# RFID_bmd200.net
KiCad netlist of a schematic drawn in EAGLE
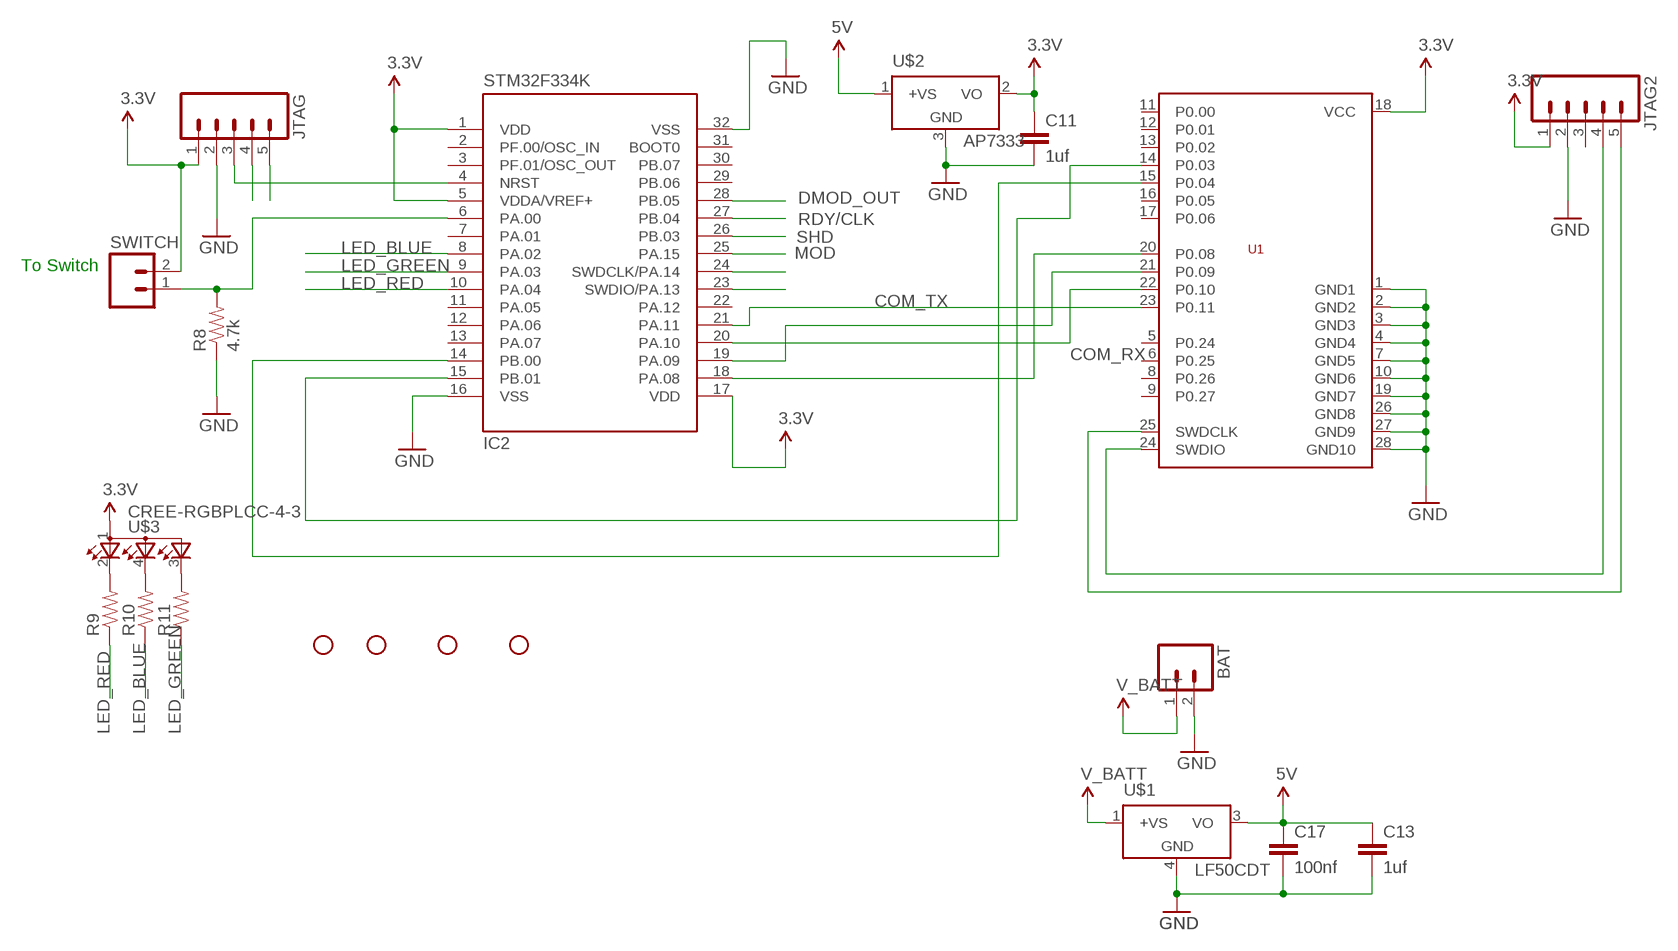
[diagram p0: schematic, sheet 1]
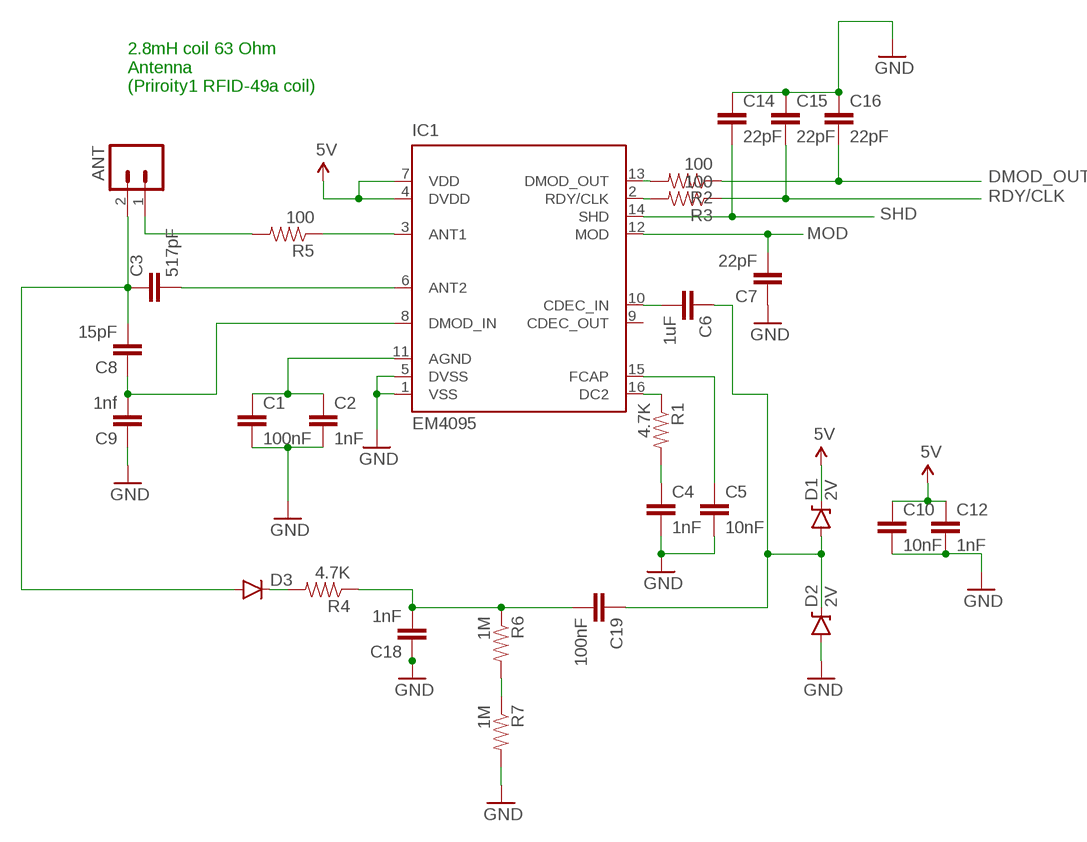
[diagram p1: schematic, sheet 2]

(export (version "E")
  (design (tool "Eeschema 10.0.6"))
  (components
    (comp (ref "ANT")
      (value "M02PTH")
      (footprint "eagle-import:1X02")
      (libsource (lib "eagle-import") (part "M02PTH"))
    )
    (comp (ref "C1")
      (value "100nF")
      (footprint "eagle-import:0805")
      (libsource (lib "eagle-import") (part "CAP0805"))
    )
    (comp (ref "C2")
      (value "1nF")
      (footprint "eagle-import:0805")
      (libsource (lib "eagle-import") (part "CAP0805"))
    )
    (comp (ref "C3")
      (value "517pF")
      (footprint "eagle-import:0805")
      (libsource (lib "eagle-import") (part "CAP0805"))
    )
    (comp (ref "C4")
      (value "1nF")
      (footprint "eagle-import:0805")
      (libsource (lib "eagle-import") (part "CAP0805"))
    )
    (comp (ref "C5")
      (value "10nF")
      (footprint "eagle-import:0805")
      (libsource (lib "eagle-import") (part "CAP0805"))
    )
    (comp (ref "C6")
      (value "1uF")
      (footprint "eagle-import:0805")
      (libsource (lib "eagle-import") (part "CAP0805"))
    )
    (comp (ref "C7")
      (value "22pF")
      (footprint "eagle-import:0805")
      (libsource (lib "eagle-import") (part "CAP0805"))
    )
    (comp (ref "C8")
      (value "15pF")
      (footprint "eagle-import:0805")
      (libsource (lib "eagle-import") (part "CAP0805"))
    )
    (comp (ref "C9")
      (value "1nf")
      (footprint "eagle-import:0805")
      (libsource (lib "eagle-import") (part "CAP0805"))
    )
    (comp (ref "C10")
      (value "10nF")
      (footprint "eagle-import:0805")
      (libsource (lib "eagle-import") (part "CAP0805"))
    )
    (comp (ref "C12")
      (value "1nF")
      (footprint "eagle-import:0805")
      (libsource (lib "eagle-import") (part "CAP0805"))
    )
    (comp (ref "C14")
      (value "22pF")
      (footprint "eagle-import:0805")
      (libsource (lib "eagle-import") (part "CAP0805"))
    )
    (comp (ref "C15")
      (value "22pF")
      (footprint "eagle-import:0805")
      (libsource (lib "eagle-import") (part "CAP0805"))
    )
    (comp (ref "C16")
      (value "22pF")
      (footprint "eagle-import:0805")
      (libsource (lib "eagle-import") (part "CAP0805"))
    )
    (comp (ref "C18")
      (value "1nF")
      (footprint "eagle-import:0805")
      (libsource (lib "eagle-import") (part "CAP0805"))
    )
    (comp (ref "C19")
      (value "100nF")
      (footprint "eagle-import:C1812")
      (libsource (lib "eagle-import") (part "CAP"))
    )
    (comp (ref "D1")
      (value "2V")
      (footprint "eagle-import:SOD-123")
      (libsource (lib "eagle-import") (part "DIODE-ZENER16V"))
    )
    (comp (ref "D2")
      (value "2V")
      (footprint "eagle-import:SOD-123")
      (libsource (lib "eagle-import") (part "DIODE-ZENER16V"))
    )
    (comp (ref "D3")
      (value "DIODESMF")
      (footprint "eagle-import:SMF")
      (libsource (lib "eagle-import") (part "DIODESMF"))
    )
    (comp (ref "IC1")
      (value "EM4095")
      (footprint "eagle-import:SO16")
      (libsource (lib "eagle-import") (part "EM4095"))
    )
    (comp (ref "R1")
      (value "4.7K")
      (footprint "eagle-import:0805")
      (libsource (lib "eagle-import") (part "RESISTOR0805-RES"))
    )
    (comp (ref "R2")
      (value "100")
      (footprint "eagle-import:0805")
      (libsource (lib "eagle-import") (part "RESISTOR0805-RES"))
    )
    (comp (ref "R3")
      (value "100")
      (footprint "eagle-import:0805")
      (libsource (lib "eagle-import") (part "RESISTOR0805-RES"))
    )
    (comp (ref "R4")
      (value "4.7K")
      (footprint "eagle-import:0805")
      (libsource (lib "eagle-import") (part "RESISTOR0805-RES"))
    )
    (comp (ref "R5")
      (value "100")
      (footprint "eagle-import:0805")
      (libsource (lib "eagle-import") (part "RESISTOR0805-RES"))
    )
    (comp (ref "R6")
      (value "1M")
      (footprint "eagle-import:0805")
      (libsource (lib "eagle-import") (part "RESISTOR0805-RES"))
    )
    (comp (ref "R7")
      (value "1M")
      (footprint "eagle-import:0805")
      (libsource (lib "eagle-import") (part "RESISTOR0805-RES"))
    )
    (comp (ref "BAT")
      (value "M02PTH")
      (footprint "eagle-import:1X02")
      (libsource (lib "eagle-import") (part "M02PTH"))
    )
    (comp (ref "C11")
      (value "1uf")
      (footprint "eagle-import:0805")
      (libsource (lib "eagle-import") (part "CAP0805"))
    )
    (comp (ref "C13")
      (value "1uf")
      (footprint "eagle-import:0805")
      (libsource (lib "eagle-import") (part "CAP0805"))
    )
    (comp (ref "C17")
      (value "100nf")
      (footprint "eagle-import:0805")
      (libsource (lib "eagle-import") (part "CAP0805"))
    )
    (comp (ref "IC2")
      (value "STM32F334K")
      (footprint "eagle-import:LQFP-32")
      (libsource (lib "eagle-import") (part "STM32F334K"))
    )
    (comp (ref "JTAG")
      (value "M05PTH")
      (footprint "eagle-import:1X05")
      (libsource (lib "eagle-import") (part "M05PTH"))
    )
    (comp (ref "JTAG2")
      (value "M05PTH")
      (footprint "eagle-import:1X05")
      (libsource (lib "eagle-import") (part "M05PTH"))
    )
    (comp (ref "R8")
      (value "4.7k")
      (footprint "eagle-import:0805")
      (libsource (lib "eagle-import") (part "RESISTOR0805-RES"))
    )
    (comp (ref "R9")
      (value "RESISTOR0805-RES")
      (footprint "eagle-import:0805")
      (libsource (lib "eagle-import") (part "RESISTOR0805-RES"))
    )
    (comp (ref "R10")
      (value "RESISTOR0805-RES")
      (footprint "eagle-import:0805")
      (libsource (lib "eagle-import") (part "RESISTOR0805-RES"))
    )
    (comp (ref "R11")
      (value "RESISTOR0805-RES")
      (footprint "eagle-import:0805")
      (libsource (lib "eagle-import") (part "RESISTOR0805-RES"))
    )
    (comp (ref "STANDOFF1")
      (value "STAND-OFF")
      (footprint "eagle-import:STAND-OFF")
      (libsource (lib "eagle-import") (part "STAND-OFF"))
    )
    (comp (ref "STANDOFF2")
      (value "STAND-OFF")
      (footprint "eagle-import:STAND-OFF")
      (libsource (lib "eagle-import") (part "STAND-OFF"))
    )
    (comp (ref "STANDOFF3")
      (value "STAND-OFF")
      (footprint "eagle-import:STAND-OFF")
      (libsource (lib "eagle-import") (part "STAND-OFF"))
    )
    (comp (ref "STANDOFF4")
      (value "STAND-OFF")
      (footprint "eagle-import:STAND-OFF")
      (libsource (lib "eagle-import") (part "STAND-OFF"))
    )
    (comp (ref "SWITCH")
      (value "M02PTH")
      (footprint "eagle-import:1X02")
      (libsource (lib "eagle-import") (part "M02PTH"))
    )
    (comp (ref "U$1")
      (value "LF50CDT")
      (footprint "eagle-import:DPACK_3")
      (libsource (lib "eagle-import") (part "LF50CDT"))
    )
    (comp (ref "U$2")
      (value "AP7333")
      (footprint "eagle-import:SOT23-3")
      (libsource (lib "eagle-import") (part "AP7333"))
    )
    (comp (ref "U$3")
      (value "CREE-RGBPLCC-4-3")
      (footprint "eagle-import:P-LCC-4-3")
      (libsource (lib "eagle-import") (part "CREE-RGBPLCC-4-3"))
    )
    (comp (ref "U1")
      (value "BMD-200")
      (footprint "eagle-import:BMD-200")
      (libsource (lib "eagle-import") (part "BMD-200"))
    )
  )
  (nets
    (net (code "1") (name "3.3V") (class "Default")
      (node (ref "C11") (pin "1") (pinfunction "1_1") (pintype "passive"))
      (node (ref "IC2") (pin "1") (pinfunction "VDD_1") (pintype "power_in"))
      (node (ref "IC2") (pin "17") (pinfunction "VDD_17") (pintype "power_in"))
      (node (ref "IC2") (pin "5") (pinfunction "VDDA/VREF+_5") (pintype "power_in"))
      (node (ref "JTAG") (pin "1") (pinfunction "1_1") (pintype "passive"))
      (node (ref "JTAG2") (pin "1") (pinfunction "1_1") (pintype "passive"))
      (node (ref "SWITCH") (pin "2") (pinfunction "2_2") (pintype "passive"))
      (node (ref "U$2") (pin "2") (pinfunction "VO_2") (pintype "input"))
      (node (ref "U$3") (pin "1") (pinfunction "A2_1") (pintype "passive"))
      (node (ref "U1") (pin "18") (pinfunction "VCC_18") (pintype "bidirectional"))
    )
    (net (code "2") (name "5V") (class "Default")
      (node (ref "C10") (pin "1") (pinfunction "1_1") (pintype "passive"))
      (node (ref "C12") (pin "1") (pinfunction "1_1") (pintype "passive"))
      (node (ref "C13") (pin "1") (pinfunction "1_1") (pintype "passive"))
      (node (ref "C17") (pin "1") (pinfunction "1_1") (pintype "passive"))
      (node (ref "D1") (pin "C") (pinfunction "C_C") (pintype "passive"))
      (node (ref "IC1") (pin "4") (pinfunction "DVDD_4") (pintype "power_in"))
      (node (ref "IC1") (pin "7") (pinfunction "VDD_7") (pintype "power_in"))
      (node (ref "U$1") (pin "3") (pinfunction "VO_3") (pintype "input"))
      (node (ref "U$2") (pin "1") (pinfunction "+VS_1") (pintype "input"))
    )
    (net (code "3") (name "COM_RX") (class "Default")
      (node (ref "IC2") (pin "20") (pinfunction "PA.10_20") (pintype "bidirectional"))
      (node (ref "U1") (pin "22") (pinfunction "P0.10_22") (pintype "bidirectional"))
    )
    (net (code "4") (name "COM_TX") (class "Default")
      (node (ref "IC2") (pin "19") (pinfunction "PA.09_19") (pintype "bidirectional"))
      (node (ref "U1") (pin "21") (pinfunction "P0.09_21") (pintype "bidirectional"))
    )
    (net (code "5") (name "DMOD_OUT") (class "Default")
      (node (ref "C16") (pin "2") (pinfunction "2_2") (pintype "passive"))
      (node (ref "IC2") (pin "28") (pinfunction "PB.05_28") (pintype "bidirectional"))
      (node (ref "R2") (pin "1") (pinfunction "1_1") (pintype "passive"))
    )
    (net (code "6") (name "GND") (class "Default")
      (node (ref "BAT") (pin "2") (pinfunction "2_2") (pintype "passive"))
      (node (ref "C1") (pin "2") (pinfunction "2_2") (pintype "passive"))
      (node (ref "C10") (pin "2") (pinfunction "2_2") (pintype "passive"))
      (node (ref "C11") (pin "2") (pinfunction "2_2") (pintype "passive"))
      (node (ref "C12") (pin "2") (pinfunction "2_2") (pintype "passive"))
      (node (ref "C13") (pin "2") (pinfunction "2_2") (pintype "passive"))
      (node (ref "C14") (pin "1") (pinfunction "1_1") (pintype "passive"))
      (node (ref "C15") (pin "1") (pinfunction "1_1") (pintype "passive"))
      (node (ref "C16") (pin "1") (pinfunction "1_1") (pintype "passive"))
      (node (ref "C17") (pin "2") (pinfunction "2_2") (pintype "passive"))
      (node (ref "C18") (pin "1") (pinfunction "1_1") (pintype "passive"))
      (node (ref "C2") (pin "2") (pinfunction "2_2") (pintype "passive"))
      (node (ref "C4") (pin "2") (pinfunction "2_2") (pintype "passive"))
      (node (ref "C5") (pin "2") (pinfunction "2_2") (pintype "passive"))
      (node (ref "C7") (pin "1") (pinfunction "1_1") (pintype "passive"))
      (node (ref "C9") (pin "1") (pinfunction "1_1") (pintype "passive"))
      (node (ref "D2") (pin "A") (pinfunction "A_A") (pintype "passive"))
      (node (ref "IC1") (pin "1") (pinfunction "VSS_1") (pintype "power_in"))
      (node (ref "IC1") (pin "5") (pinfunction "DVSS_5") (pintype "power_in"))
      (node (ref "IC2") (pin "16") (pinfunction "VSS_16") (pintype "power_in"))
      (node (ref "IC2") (pin "32") (pinfunction "VSS_32") (pintype "power_in"))
      (node (ref "JTAG") (pin "2") (pinfunction "2_2") (pintype "passive"))
      (node (ref "JTAG2") (pin "2") (pinfunction "2_2") (pintype "passive"))
      (node (ref "R7") (pin "2") (pinfunction "2_2") (pintype "passive"))
      (node (ref "R8") (pin "1") (pinfunction "1_1") (pintype "passive"))
      (node (ref "U$1") (pin "4") (pinfunction "GND_4") (pintype "power_in"))
      (node (ref "U$2") (pin "3") (pinfunction "GND_3") (pintype "power_in"))
      (node (ref "U1") (pin "1") (pinfunction "GND1_1") (pintype "bidirectional"))
      (node (ref "U1") (pin "10") (pinfunction "GND6_10") (pintype "bidirectional"))
      (node (ref "U1") (pin "19") (pinfunction "GND7_19") (pintype "bidirectional"))
      (node (ref "U1") (pin "2") (pinfunction "GND2_2") (pintype "bidirectional"))
      (node (ref "U1") (pin "26") (pinfunction "GND8_26") (pintype "bidirectional"))
      (node (ref "U1") (pin "27") (pinfunction "GND9_27") (pintype "bidirectional"))
      (node (ref "U1") (pin "28") (pinfunction "GND10_28") (pintype "bidirectional"))
      (node (ref "U1") (pin "3") (pinfunction "GND3_3") (pintype "bidirectional"))
      (node (ref "U1") (pin "4") (pinfunction "GND4_4") (pintype "bidirectional"))
      (node (ref "U1") (pin "7") (pinfunction "GND5_7") (pintype "bidirectional"))
    )
    (net (code "7") (name "LED_BLUE") (class "Default")
      (node (ref "IC2") (pin "8") (pinfunction "PA.02_8") (pintype "bidirectional"))
      (node (ref "R10") (pin "1") (pinfunction "1_1") (pintype "passive"))
    )
    (net (code "8") (name "LED_GREEN") (class "Default")
      (node (ref "IC2") (pin "9") (pinfunction "PA.03_9") (pintype "bidirectional"))
      (node (ref "R11") (pin "1") (pinfunction "1_1") (pintype "passive"))
    )
    (net (code "9") (name "LED_RED") (class "Default")
      (node (ref "IC2") (pin "10") (pinfunction "PA.04_10") (pintype "bidirectional"))
      (node (ref "R9") (pin "1") (pinfunction "1_1") (pintype "passive"))
    )
    (net (code "10") (name "MOD") (class "Default")
      (node (ref "C7") (pin "2") (pinfunction "2_2") (pintype "passive"))
      (node (ref "IC1") (pin "12") (pinfunction "MOD_12") (pintype "input"))
      (node (ref "IC2") (pin "25") (pinfunction "PA.15_25") (pintype "bidirectional"))
    )
    (net (code "11") (name "Net-(ANT-Pad1)") (class "Default")
      (node (ref "ANT") (pin "1") (pinfunction "1_1") (pintype "passive"))
      (node (ref "R5") (pin "2") (pinfunction "2_2") (pintype "passive"))
    )
    (net (code "12") (name "Net-(C4-Pad1)") (class "Default")
      (node (ref "C4") (pin "1") (pinfunction "1_1") (pintype "passive"))
      (node (ref "R1") (pin "2") (pinfunction "2_2") (pintype "passive"))
    )
    (net (code "13") (name "Net-(C18-Pad2)") (class "Default")
      (node (ref "C18") (pin "2") (pinfunction "2_2") (pintype "passive"))
      (node (ref "C19") (pin "2") (pinfunction "2_2") (pintype "passive"))
      (node (ref "R4") (pin "1") (pinfunction "1_1") (pintype "passive"))
      (node (ref "R6") (pin "1") (pinfunction "1_1") (pintype "passive"))
    )
    (net (code "14") (name "Net-(C19-Pad1)") (class "Default")
      (node (ref "C19") (pin "1") (pinfunction "1_1") (pintype "passive"))
      (node (ref "C6") (pin "1") (pinfunction "1_1") (pintype "passive"))
      (node (ref "D1") (pin "A") (pinfunction "A_A") (pintype "passive"))
      (node (ref "D2") (pin "C") (pinfunction "C_C") (pintype "passive"))
    )
    (net (code "15") (name "Net-(D3-A)") (class "Default")
      (node (ref "ANT") (pin "2") (pinfunction "2_2") (pintype "passive"))
      (node (ref "C3") (pin "1") (pinfunction "1_1") (pintype "passive"))
      (node (ref "C8") (pin "2") (pinfunction "2_2") (pintype "passive"))
      (node (ref "D3") (pin "P$2") (pinfunction "A_P$2") (pintype "passive"))
    )
    (net (code "16") (name "Net-(D3-C)") (class "Default")
      (node (ref "D3") (pin "P$1") (pinfunction "C_P$1") (pintype "passive"))
      (node (ref "R4") (pin "2") (pinfunction "2_2") (pintype "passive"))
    )
    (net (code "17") (name "Net-(IC1-AGND)") (class "Default")
      (node (ref "C1") (pin "1") (pinfunction "1_1") (pintype "passive"))
      (node (ref "C2") (pin "1") (pinfunction "1_1") (pintype "passive"))
      (node (ref "IC1") (pin "11") (pinfunction "AGND_11") (pintype "power_in"))
    )
    (net (code "18") (name "Net-(IC1-ANT1)") (class "Default")
      (node (ref "IC1") (pin "3") (pinfunction "ANT1_3") (pintype "passive"))
      (node (ref "R5") (pin "1") (pinfunction "1_1") (pintype "passive"))
    )
    (net (code "19") (name "Net-(IC1-ANT2)") (class "Default")
      (node (ref "C3") (pin "2") (pinfunction "2_2") (pintype "passive"))
      (node (ref "IC1") (pin "6") (pinfunction "ANT2_6") (pintype "passive"))
    )
    (net (code "20") (name "Net-(IC1-CDEC_IN)") (class "Default")
      (node (ref "C6") (pin "2") (pinfunction "2_2") (pintype "passive"))
      (node (ref "IC1") (pin "10") (pinfunction "CDEC_IN_10") (pintype "input"))
    )
    (net (code "21") (name "Net-(IC1-DC2)") (class "Default")
      (node (ref "IC1") (pin "16") (pinfunction "DC2_16") (pintype "passive"))
      (node (ref "R1") (pin "1") (pinfunction "1_1") (pintype "passive"))
    )
    (net (code "22") (name "Net-(IC1-DMOD_IN)") (class "Default")
      (node (ref "C8") (pin "1") (pinfunction "1_1") (pintype "passive"))
      (node (ref "C9") (pin "2") (pinfunction "2_2") (pintype "passive"))
      (node (ref "IC1") (pin "8") (pinfunction "DMOD_IN_8") (pintype "input"))
    )
    (net (code "23") (name "Net-(IC1-DMOD_OUT)") (class "Default")
      (node (ref "IC1") (pin "13") (pinfunction "DMOD_OUT_13") (pintype "output"))
      (node (ref "R2") (pin "2") (pinfunction "2_2") (pintype "passive"))
    )
    (net (code "24") (name "Net-(IC1-FCAP)") (class "Default")
      (node (ref "C5") (pin "1") (pinfunction "1_1") (pintype "passive"))
      (node (ref "IC1") (pin "15") (pinfunction "FCAP_15") (pintype "passive"))
    )
    (net (code "25") (name "Net-(IC1-RDY{slash}CLK)") (class "Default")
      (node (ref "IC1") (pin "2") (pinfunction "RDY/CLK_2") (pintype "output"))
      (node (ref "R3") (pin "2") (pinfunction "2_2") (pintype "passive"))
    )
    (net (code "26") (name "Net-(IC2-NRST)") (class "Default")
      (node (ref "IC2") (pin "4") (pinfunction "NRST_4") (pintype "bidirectional"))
      (node (ref "JTAG") (pin "3") (pinfunction "3_3") (pintype "passive"))
    )
    (net (code "27") (name "Net-(IC2-PA.00)") (class "Default")
      (node (ref "IC2") (pin "6") (pinfunction "PA.00_6") (pintype "bidirectional"))
      (node (ref "R8") (pin "2") (pinfunction "2_2") (pintype "passive"))
      (node (ref "SWITCH") (pin "1") (pinfunction "1_1") (pintype "passive"))
    )
    (net (code "28") (name "Net-(IC2-PA.08)") (class "Default")
      (node (ref "IC2") (pin "18") (pinfunction "PA.08_18") (pintype "bidirectional"))
      (node (ref "U1") (pin "20") (pinfunction "P0.08_20") (pintype "bidirectional"))
    )
    (net (code "29") (name "Net-(IC2-PA.11)") (class "Default")
      (node (ref "IC2") (pin "21") (pinfunction "PA.11_21") (pintype "bidirectional"))
      (node (ref "U1") (pin "23") (pinfunction "P0.11_23") (pintype "bidirectional"))
    )
    (net (code "30") (name "Net-(IC2-PB.00)") (class "Default")
      (node (ref "IC2") (pin "14") (pinfunction "PB.00_14") (pintype "bidirectional"))
      (node (ref "U1") (pin "15") (pinfunction "P0.04_15") (pintype "bidirectional"))
    )
    (net (code "31") (name "Net-(IC2-PB.01)") (class "Default")
      (node (ref "IC2") (pin "15") (pinfunction "PB.01_15") (pintype "bidirectional"))
      (node (ref "U1") (pin "14") (pinfunction "P0.03_14") (pintype "bidirectional"))
    )
    (net (code "32") (name "Net-(R6-Pad2)") (class "Default")
      (node (ref "R6") (pin "2") (pinfunction "2_2") (pintype "passive"))
      (node (ref "R7") (pin "1") (pinfunction "1_1") (pintype "passive"))
    )
    (net (code "33") (name "Net-(U$3-CBLUE)") (class "Default")
      (node (ref "R10") (pin "2") (pinfunction "2_2") (pintype "passive"))
      (node (ref "U$3") (pin "4") (pinfunction "CBLUE_4") (pintype "passive"))
    )
    (net (code "34") (name "Net-(U$3-CGREEN)") (class "Default")
      (node (ref "R11") (pin "2") (pinfunction "2_2") (pintype "passive"))
      (node (ref "U$3") (pin "3") (pinfunction "CGREEN_3") (pintype "passive"))
    )
    (net (code "35") (name "Net-(U$3-CRED)") (class "Default")
      (node (ref "R9") (pin "2") (pinfunction "2_2") (pintype "passive"))
      (node (ref "U$3") (pin "2") (pinfunction "CRED_2") (pintype "passive"))
    )
    (net (code "36") (name "Net-(U1-SWDCLK)") (class "Default")
      (node (ref "JTAG2") (pin "5") (pinfunction "5_5") (pintype "passive"))
      (node (ref "U1") (pin "25") (pinfunction "SWDCLK_25") (pintype "bidirectional"))
    )
    (net (code "37") (name "Net-(U1-SWDIO)") (class "Default")
      (node (ref "JTAG2") (pin "4") (pinfunction "4_4") (pintype "passive"))
      (node (ref "U1") (pin "24") (pinfunction "SWDIO_24") (pintype "bidirectional"))
    )
    (net (code "38") (name "RDY{slash}CLK") (class "Default")
      (node (ref "C15") (pin "2") (pinfunction "2_2") (pintype "passive"))
      (node (ref "IC2") (pin "27") (pinfunction "PB.04_27") (pintype "bidirectional"))
      (node (ref "R3") (pin "1") (pinfunction "1_1") (pintype "passive"))
    )
    (net (code "39") (name "SHD") (class "Default")
      (node (ref "C14") (pin "2") (pinfunction "2_2") (pintype "passive"))
      (node (ref "IC1") (pin "14") (pinfunction "SHD_14") (pintype "input"))
      (node (ref "IC2") (pin "26") (pinfunction "PB.03_26") (pintype "bidirectional"))
    )
    (net (code "40") (name "STM_SWDCLK") (class "Default")
      (node (ref "IC2") (pin "24") (pinfunction "SWDCLK/PA.14_24") (pintype "bidirectional"))
      (node (ref "JTAG") (pin "5") (pinfunction "5_5") (pintype "passive"))
    )
    (net (code "41") (name "STM_SWDIO") (class "Default")
      (node (ref "IC2") (pin "23") (pinfunction "SWDIO/PA.13_23") (pintype "bidirectional"))
      (node (ref "JTAG") (pin "4") (pinfunction "4_4") (pintype "passive"))
    )
    (net (code "42") (name "V_BATT") (class "Default")
      (node (ref "BAT") (pin "1") (pinfunction "1_1") (pintype "passive"))
      (node (ref "U$1") (pin "1") (pinfunction "+VS_1") (pintype "input"))
    )
    (net (code "43") (name "unconnected-(IC1-CDEC_OUT-Pad9)") (class "Default")
      (node (ref "IC1") (pin "9") (pinfunction "CDEC_OUT_9") (pintype "output"))
    )
    (net (code "44") (name "unconnected-(IC2-BOOT0-Pad31)") (class "Default")
      (node (ref "IC2") (pin "31") (pinfunction "BOOT0_31") (pintype "bidirectional"))
    )
    (net (code "45") (name "unconnected-(IC2-PA.01-Pad7)") (class "Default")
      (node (ref "IC2") (pin "7") (pinfunction "PA.01_7") (pintype "bidirectional"))
    )
    (net (code "46") (name "unconnected-(IC2-PA.05-Pad11)") (class "Default")
      (node (ref "IC2") (pin "11") (pinfunction "PA.05_11") (pintype "bidirectional"))
    )
    (net (code "47") (name "unconnected-(IC2-PA.06-Pad12)") (class "Default")
      (node (ref "IC2") (pin "12") (pinfunction "PA.06_12") (pintype "bidirectional"))
    )
    (net (code "48") (name "unconnected-(IC2-PA.07-Pad13)") (class "Default")
      (node (ref "IC2") (pin "13") (pinfunction "PA.07_13") (pintype "bidirectional"))
    )
    (net (code "49") (name "unconnected-(IC2-PA.12-Pad22)") (class "Default")
      (node (ref "IC2") (pin "22") (pinfunction "PA.12_22") (pintype "bidirectional"))
    )
    (net (code "50") (name "unconnected-(IC2-PB.06-Pad29)") (class "Default")
      (node (ref "IC2") (pin "29") (pinfunction "PB.06_29") (pintype "bidirectional"))
    )
    (net (code "51") (name "unconnected-(IC2-PB.07-Pad30)") (class "Default")
      (node (ref "IC2") (pin "30") (pinfunction "PB.07_30") (pintype "bidirectional"))
    )
    (net (code "52") (name "unconnected-(IC2-PF.00{slash}OSC_IN-Pad2)") (class "Default")
      (node (ref "IC2") (pin "2") (pinfunction "PF.00/OSC_IN_2") (pintype "bidirectional"))
    )
    (net (code "53") (name "unconnected-(IC2-PF.01{slash}OSC_OUT-Pad3)") (class "Default")
      (node (ref "IC2") (pin "3") (pinfunction "PF.01/OSC_OUT_3") (pintype "bidirectional"))
    )
    (net (code "54") (name "unconnected-(JTAG2-Pad3)") (class "Default")
      (node (ref "JTAG2") (pin "3") (pinfunction "3_3") (pintype "passive"))
    )
    (net (code "55") (name "unconnected-(U1-P0.00-Pad11)") (class "Default")
      (node (ref "U1") (pin "11") (pinfunction "P0.00_11") (pintype "bidirectional"))
    )
    (net (code "56") (name "unconnected-(U1-P0.01-Pad12)") (class "Default")
      (node (ref "U1") (pin "12") (pinfunction "P0.01_12") (pintype "bidirectional"))
    )
    (net (code "57") (name "unconnected-(U1-P0.02-Pad13)") (class "Default")
      (node (ref "U1") (pin "13") (pinfunction "P0.02_13") (pintype "bidirectional"))
    )
    (net (code "58") (name "unconnected-(U1-P0.05-Pad16)") (class "Default")
      (node (ref "U1") (pin "16") (pinfunction "P0.05_16") (pintype "bidirectional"))
    )
    (net (code "59") (name "unconnected-(U1-P0.06-Pad17)") (class "Default")
      (node (ref "U1") (pin "17") (pinfunction "P0.06_17") (pintype "bidirectional"))
    )
    (net (code "60") (name "unconnected-(U1-P0.24-Pad5)") (class "Default")
      (node (ref "U1") (pin "5") (pinfunction "P0.24_5") (pintype "bidirectional"))
    )
    (net (code "61") (name "unconnected-(U1-P0.25-Pad6)") (class "Default")
      (node (ref "U1") (pin "6") (pinfunction "P0.25_6") (pintype "bidirectional"))
    )
    (net (code "62") (name "unconnected-(U1-P0.26-Pad8)") (class "Default")
      (node (ref "U1") (pin "8") (pinfunction "P0.26_8") (pintype "bidirectional"))
    )
    (net (code "63") (name "unconnected-(U1-P0.27-Pad9)") (class "Default")
      (node (ref "U1") (pin "9") (pinfunction "P0.27_9") (pintype "bidirectional"))
    )
  )
)
